# Main.net
KiCad netlist of a schematic drawn in Altium Designer
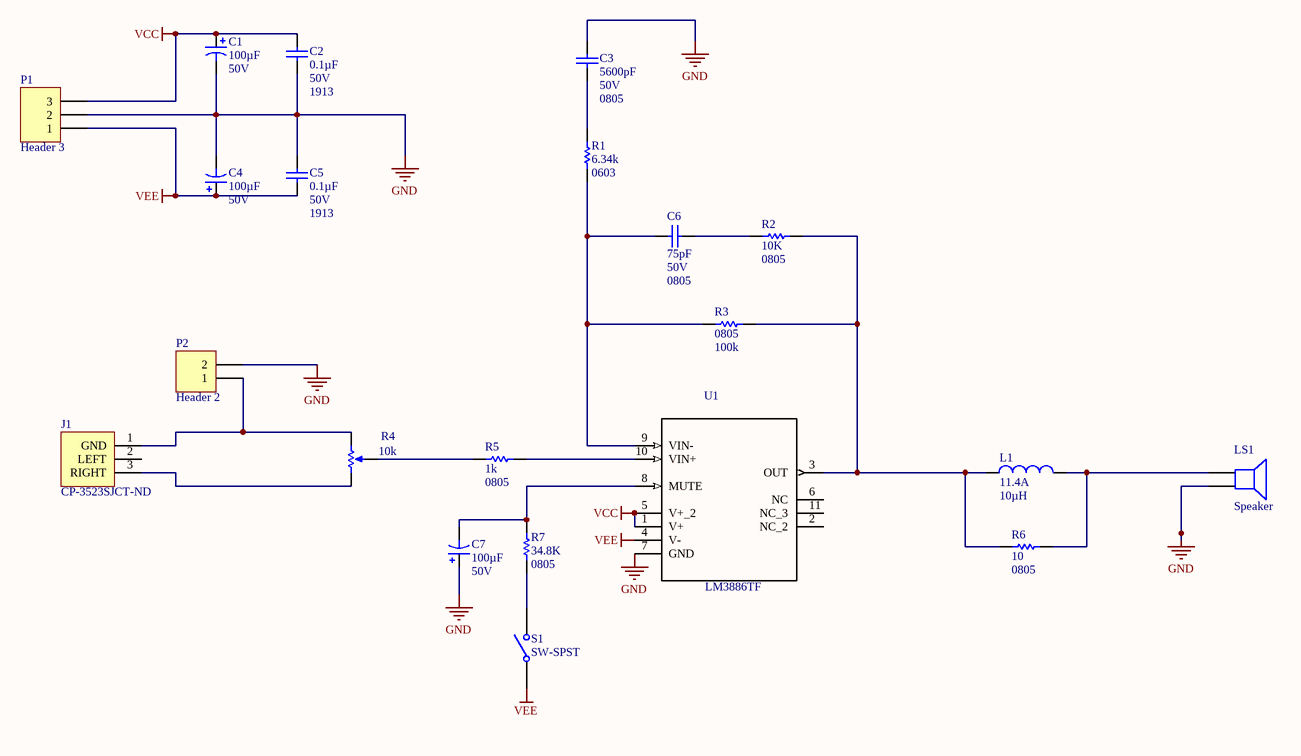
[diagram p0: Main.SchDoc]

(export (version "E")
  (design (tool "Eeschema 10.0.6"))
  (components
    (comp (ref "C1")
      (value "UUQ1H101MCL1GS")
      (footprint "CAPAE109103X103M")
      (description "CAP ALUM 100UF 20% 50V SMD")
      (fields
        (field (name "TOLERANCE") "±20%")
        (field (name "CAPACITANCE") "100µF")
        (field (name "VOLTAGE - RATED") "50V")
      )
      (libsource (lib "Capacitors") (part "UUQ1H101MCL1GS"))
    )
    (comp (ref "C2")
      (value "ECH-U1H104JX9")
      (footprint "CAP1913")
      (description "CAP FILM 0.1UF 5% 50VDC 1913")
      (fields
        (field (name "TOLERANCE") "±5%")
        (field (name "CAPACITANCE") "0.1µF")
        (field (name "VOLTAGE RATING - DC") "50V")
        (field (name "PACKAGE / CASE") "1913")
      )
      (libsource (lib "Capacitors") (part "ECH-U1H104JX9"))
    )
    (comp (ref "C3")
      (value "C2012C0G1H562J060AA")
      (footprint "CAP0805")
      (description "CAP CER 5600PF 50V C0G 0805")
      (fields
        (field (name "CAPACITANCE") "5600pF")
        (field (name "VOLTAGE - RATED") "50V")
        (field (name "PACKAGE") "0805")
      )
      (libsource (lib "Capacitors") (part "C2012C0G1H562J060AA"))
    )
    (comp (ref "C4")
      (value "UUQ1H101MCL1GS")
      (footprint "CAPAE109103X103M")
      (description "CAP ALUM 100UF 20% 50V SMD")
      (fields
        (field (name "TOLERANCE") "±20%")
        (field (name "CAPACITANCE") "100µF")
        (field (name "VOLTAGE - RATED") "50V")
      )
      (libsource (lib "Capacitors") (part "UUQ1H101MCL1GS"))
    )
    (comp (ref "C5")
      (value "ECH-U1H104JX9")
      (footprint "CAP1913")
      (description "CAP FILM 0.1UF 5% 50VDC 1913")
      (fields
        (field (name "TOLERANCE") "±5%")
        (field (name "CAPACITANCE") "0.1µF")
        (field (name "VOLTAGE RATING - DC") "50V")
        (field (name "PACKAGE / CASE") "1913")
      )
      (libsource (lib "Capacitors") (part "ECH-U1H104JX9"))
    )
    (comp (ref "C6")
      (value "C0805C750J5GAC7800")
      (footprint "CAP0805")
      (description "CAP CER 75PF 50V NP0 0805")
      (fields
        (field (name "CAPACITANCE") "75pF")
        (field (name "VOLTAGE - RATED") "50V")
        (field (name "PACKAGE") "0805")
      )
      (libsource (lib "Capacitors") (part "C0805C750J5GAC7800"))
    )
    (comp (ref "C7")
      (value "UUQ1H101MCL1GS")
      (footprint "CAPAE109103X103M")
      (description "CAP ALUM 100UF 20% 50V SMD")
      (fields
        (field (name "TOLERANCE") "±20%")
        (field (name "CAPACITANCE") "100µF")
        (field (name "VOLTAGE - RATED") "50V")
      )
      (libsource (lib "Capacitors") (part "UUQ1H101MCL1GS"))
    )
    (comp (ref "J1")
      (value "SJ-3523-SMT-TR")
      (footprint "CONN JACK STEREO 3.5MM SMD R/A")
      (description "CONN JACK STEREO 3.5MM SMD R/A")
      (fields (field (name "SUPPLIER PART NUMBER 1") "CP-3523SJCT-ND"))
      (libsource (lib "Mechanical_Devices") (part "SJ-3523-SMT-TR"))
    )
    (comp (ref "L1")
      (value "2100LL-100-V-RC")
      (footprint "Shielded Toroidal Inductor")
      (description "FIXED IND 10UH 11.4A 5 MOHM TH")
      (fields
        (field (name "TOLERANCE") "±15%")
        (field (name "CURRENT RATING") "11.4A")
        (field (name "INDUCTANCE") "10µH")
      )
      (libsource (lib "Inductors") (part "2100LL-100-V-RC"))
    )
    (comp (ref "LS1")
      (value "Speaker")
      (footprint "PIN2")
      (description "Loudspeaker")
      (fields (field (name "PUBLISHER") "Altium Limited"))
      (libsource (lib "Miscellaneous Devices") (part "Speaker"))
    )
    (comp (ref "P1")
      (value "Header 3")
      (footprint "HDR1X3")
      (description "Header, 3-Pin")
      (fields (field (name "PUBLISHER") "Altium Limited"))
      (libsource (lib "Miscellaneous Connectors") (part "Header 3"))
    )
    (comp (ref "P2")
      (value "Header 2")
      (footprint "HDR1X2")
      (description "Header, 2-Pin")
      (fields (field (name "PUBLISHER") "Altium Limited"))
      (libsource (lib "Miscellaneous Connectors") (part "Header 2"))
    )
    (comp (ref "R1")
      (value "RT0603DRD076K34L")
      (footprint "RES0603")
      (description "RES SMD 6.34KOHM 0.5% 1/10W 0603")
      (fields (field (name "RESISTANCE") "6.34k") (field (name "PACKAGE") "0603"))
      (libsource (lib "Resistors") (part "RT0603DRD076K34L"))
    )
    (comp (ref "R2")
      (value "RT0805BRE0710KL")
      (footprint "RES0805")
      (description "RES SMD 10K OHM 0.1% 1/8W 0805")
      (fields (field (name "RESISTANCE") "10K") (field (name "PACKAGE") "0805"))
      (libsource (lib "Resistors") (part "RT0805BRE0710KL"))
    )
    (comp (ref "R3")
      (value "ERA-6AEB104V")
      (footprint "RES0805")
      (description "RES SMD 100K OHM 0.1% 1/8W 0805")
      (fields (field (name "PACKAGE") "0805") (field (name "RESISTANCE") "100k"))
      (libsource (lib "Resistors") (part "ERA-6AEB104V"))
    )
    (comp (ref "R4")
      (value "10k")
      (footprint "VR5")
      (description "Potentiometer")
      (fields (field (name "Comment") "RPot") (field (name "PUBLISHER") "Altium Limited"))
      (libsource (lib "Miscellaneous Devices") (part "RPot"))
    )
    (comp (ref "R5")
      (value "RT0805FRE071KL")
      (footprint "RES0805")
      (description "RES SMD 1K OHM 1% 1/8W 0805")
      (fields (field (name "RESISTANCE") "1k") (field (name "PACKAGE") "0805"))
      (libsource (lib "Resistors") (part "RT0805FRE071KL"))
    )
    (comp (ref "R6")
      (value "RNCP0805FTD10R0")
      (footprint "RES0805")
      (description "RES 10 OHM 1% 1/4W 0805")
      (fields
        (field (name "TOLERANCE") "±1%")
        (field (name "RESISTANCE") "10")
        (field (name "PACKAGE") "0805")
      )
      (libsource (lib "Resistors") (part "RNCP0805FTD10R0"))
    )
    (comp (ref "R7")
      (value "RT0805DRD0734K8L")
      (footprint "RES0805")
      (description "RES SMD 34.8K OHM 0.5% 1/8W 0805")
      (fields (field (name "RESISTANCE") "34.8K") (field (name "PACKAGE") "0805"))
      (libsource (lib "Resistors") (part "RT0805DRD0734K8L"))
    )
    (comp (ref "S1")
      (value "SW-SPST")
      (footprint "SPST-2")
      (description "Single-Pole, Single-Throw Switch")
      (fields (field (name "PUBLISHER") "Altium Limited"))
      (libsource (lib "Miscellaneous Devices") (part "SW-SPST"))
    )
    (comp (ref "U1")
      (value "LM3886TF")
      (footprint "AMP_LM3886T")
      (fields (field (name "MF") "Texas"))
      (libsource (lib "LM3886TF") (part "LM3886TF"))
    )
  )
  (nets
    (net (code "1") (name "GND") (class "Default")
      (node (ref "C1") (pin "2") (pinfunction "2_2") (pintype "passive"))
      (node (ref "C2") (pin "1") (pinfunction "1_1") (pintype "passive"))
      (node (ref "C3") (pin "2") (pinfunction "2_2") (pintype "passive"))
      (node (ref "C4") (pin "2") (pinfunction "2_2") (pintype "passive"))
      (node (ref "C5") (pin "2") (pinfunction "2_2") (pintype "passive"))
      (node (ref "C7") (pin "1") (pinfunction "1_1") (pintype "passive"))
      (node (ref "LS1") (pin "2") (pinfunction "2_2") (pintype "passive"))
      (node (ref "P1") (pin "2") (pinfunction "2_2") (pintype "passive"))
      (node (ref "P2") (pin "2") (pinfunction "2_2") (pintype "passive"))
      (node (ref "U1") (pin "7") (pinfunction "GND_7") (pintype "power_in"))
    )
    (net (code "2") (name "Net-(C3-Pad1)") (class "Default")
      (node (ref "C3") (pin "1") (pinfunction "1_1") (pintype "passive"))
      (node (ref "R1") (pin "2") (pinfunction "2_2") (pintype "passive"))
    )
    (net (code "3") (name "Net-(C6-Pad2)") (class "Default")
      (node (ref "C6") (pin "2") (pinfunction "2_2") (pintype "passive"))
      (node (ref "R2") (pin "1") (pinfunction "1_1") (pintype "passive"))
    )
    (net (code "4") (name "Net-(J1-GND)") (class "Default")
      (node (ref "J1") (pin "1") (pinfunction "GND_1") (pintype "passive"))
      (node (ref "P2") (pin "1") (pinfunction "1_1") (pintype "passive"))
      (node (ref "R4") (pin "2") (pinfunction "BOT_2") (pintype "passive"))
    )
    (net (code "5") (name "Net-(J1-RIGHT)") (class "Default")
      (node (ref "J1") (pin "3") (pinfunction "RIGHT_3") (pintype "passive"))
      (node (ref "R4") (pin "1") (pinfunction "TOP_1") (pintype "passive"))
    )
    (net (code "6") (name "Net-(L1-Pad2)") (class "Default")
      (node (ref "L1") (pin "2") (pinfunction "2_2") (pintype "passive"))
      (node (ref "LS1") (pin "1") (pinfunction "1_1") (pintype "passive"))
      (node (ref "R6") (pin "2") (pinfunction "2_2") (pintype "passive"))
    )
    (net (code "7") (name "Net-(R4-TAP)") (class "Default")
      (node (ref "R4") (pin "3") (pinfunction "TAP_3") (pintype "passive"))
      (node (ref "R5") (pin "1") (pinfunction "1_1") (pintype "passive"))
    )
    (net (code "8") (name "Net-(S1-NO)") (class "Default")
      (node (ref "R7") (pin "1") (pinfunction "1_1") (pintype "passive"))
      (node (ref "S1") (pin "2") (pinfunction "NO_2") (pintype "passive"))
    )
    (net (code "9") (name "Net-(U1-MUTE)") (class "Default")
      (node (ref "C7") (pin "2") (pinfunction "2_2") (pintype "passive"))
      (node (ref "R7") (pin "2") (pinfunction "2_2") (pintype "passive"))
      (node (ref "U1") (pin "8") (pinfunction "MUTE_8") (pintype "input"))
    )
    (net (code "10") (name "Net-(U1-OUT)") (class "Default")
      (node (ref "L1") (pin "1") (pinfunction "1_1") (pintype "passive"))
      (node (ref "R2") (pin "2") (pinfunction "2_2") (pintype "passive"))
      (node (ref "R3") (pin "2") (pinfunction "2_2") (pintype "passive"))
      (node (ref "R6") (pin "1") (pinfunction "1_1") (pintype "passive"))
      (node (ref "U1") (pin "3") (pinfunction "OUT_3") (pintype "output"))
    )
    (net (code "11") (name "Net-(U1-VIN+)") (class "Default")
      (node (ref "R5") (pin "2") (pinfunction "2_2") (pintype "passive"))
      (node (ref "U1") (pin "10") (pinfunction "VIN+_10") (pintype "input"))
    )
    (net (code "12") (name "Net-(U1-VIN-)") (class "Default")
      (node (ref "C6") (pin "1") (pinfunction "1_1") (pintype "passive"))
      (node (ref "R1") (pin "1") (pinfunction "1_1") (pintype "passive"))
      (node (ref "R3") (pin "1") (pinfunction "1_1") (pintype "passive"))
      (node (ref "U1") (pin "9") (pinfunction "VIN-_9") (pintype "input"))
    )
    (net (code "13") (name "VCC") (class "Default")
      (node (ref "C1") (pin "1") (pinfunction "1_1") (pintype "passive"))
      (node (ref "C2") (pin "2") (pinfunction "2_2") (pintype "passive"))
      (node (ref "P1") (pin "3") (pinfunction "3_3") (pintype "passive"))
      (node (ref "U1") (pin "1") (pinfunction "V+_1") (pintype "power_in"))
      (node (ref "U1") (pin "5") (pinfunction "V+_2_5") (pintype "power_in"))
    )
    (net (code "14") (name "VEE") (class "Default")
      (node (ref "C4") (pin "1") (pinfunction "1_1") (pintype "passive"))
      (node (ref "C5") (pin "1") (pinfunction "1_1") (pintype "passive"))
      (node (ref "P1") (pin "1") (pinfunction "1_1") (pintype "passive"))
      (node (ref "S1") (pin "1") (pinfunction "COMMON_1") (pintype "passive"))
      (node (ref "U1") (pin "4") (pinfunction "V-_4") (pintype "power_in"))
    )
    (net (code "15") (name "unconnected-(J1-LEFT-Pad2)") (class "Default")
      (node (ref "J1") (pin "2") (pinfunction "LEFT_2") (pintype "passive"))
    )
    (net (code "16") (name "unconnected-(U1-NC-Pad6)") (class "Default")
      (node (ref "U1") (pin "6") (pinfunction "NC_6") (pintype "passive"))
    )
    (net (code "17") (name "unconnected-(U1-NC_2-Pad2)") (class "Default")
      (node (ref "U1") (pin "2") (pinfunction "NC_2_2") (pintype "passive"))
    )
    (net (code "18") (name "unconnected-(U1-NC_3-Pad11)") (class "Default")
      (node (ref "U1") (pin "11") (pinfunction "NC_3_11") (pintype "passive"))
    )
  )
)
